# Connectors.net
KiCad netlist of a schematic drawn in Altium Designer
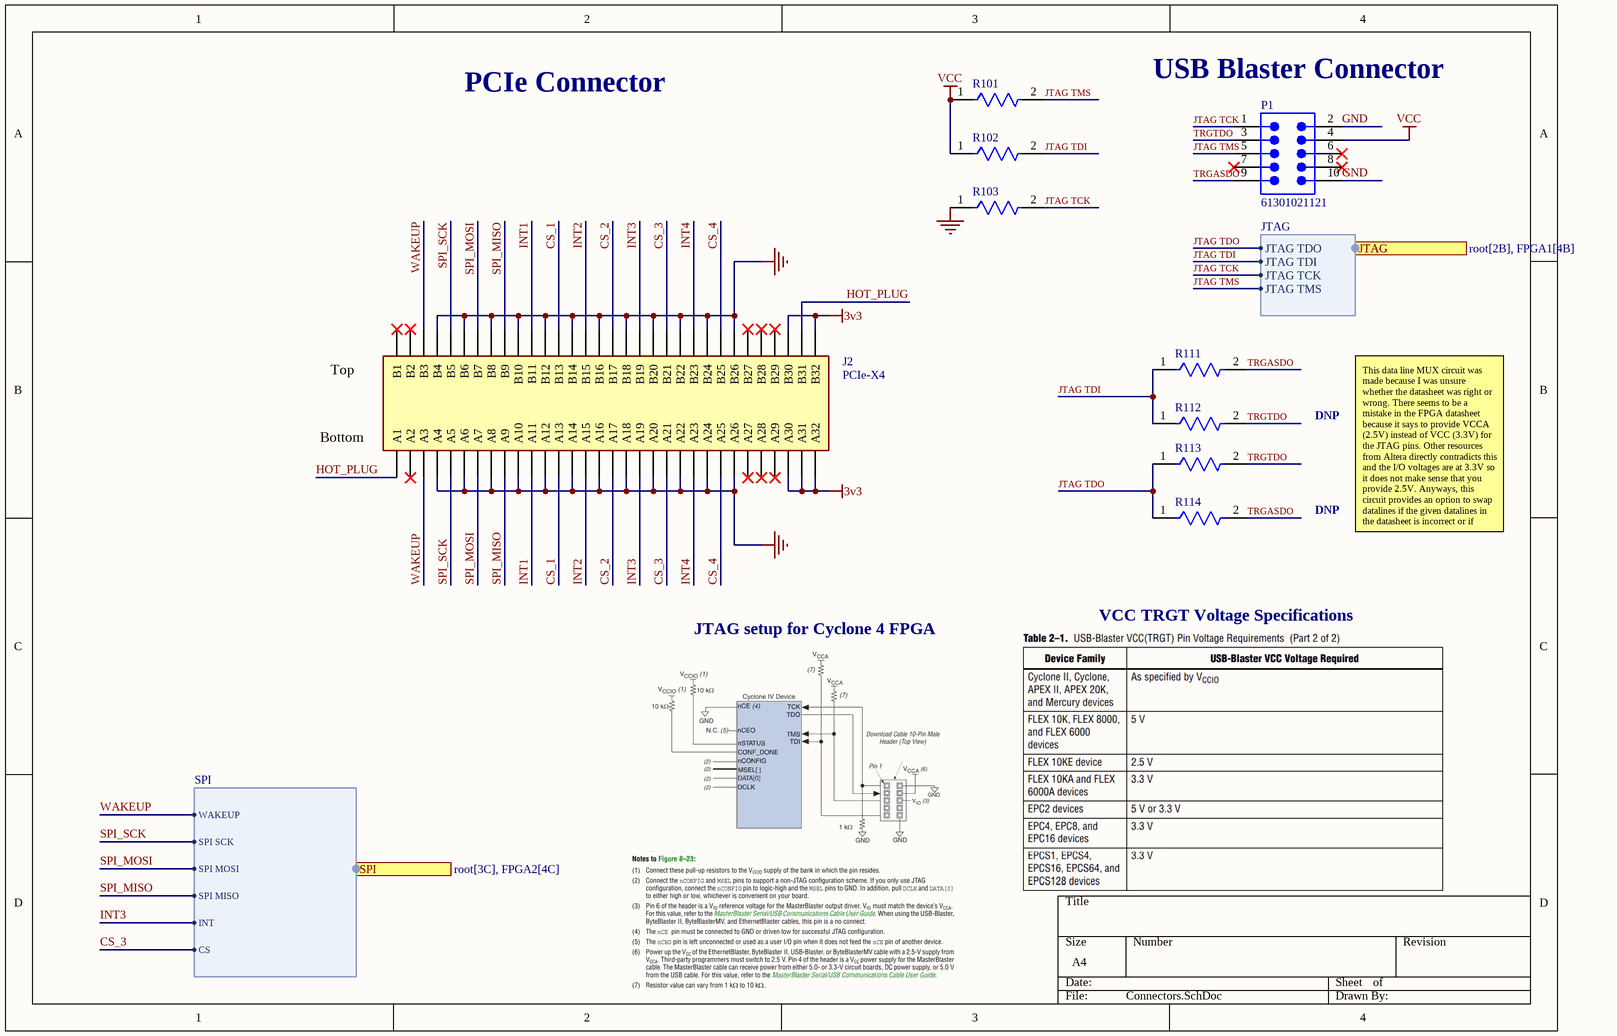
[diagram p0: Connectors.SchDoc]

(export (version "E")
  (design (tool "Eeschema 10.0.6"))
  (components
    (comp (ref "J2")
      (value "PCIe-X4")
      (footprint "BUS_PCIexpress_x4")
      (libsource (lib "FC") (part "PCIe-X4"))
    )
    (comp (ref "P1")
      (value "61301021121")
      (footprint "61301021121")
      (description "THT Vertical Pin Header WR-PHD, Pitch 2.54 mm, Dual Row, 10 pins")
      (libsource (lib "Altium Content Vault") (part "Header_Male_2R_10P"))
    )
    (comp (ref "R101")
      (value "RC0402FR-071KL")
      (footprint "FP-RC0402-0_4-IPC_A")
      (description "RES 1K OHM 1% 1/16W 0402")
      (fields (field (name "TOLERANCE") "1%"))
      (libsource (lib "Altium Content Vault") (part "1029c3af85768c4190bb7ad29bc67b5"))
    )
    (comp (ref "R102")
      (value "RC0402FR-071KL")
      (footprint "FP-RC0402-0_4-IPC_A")
      (description "RES 1K OHM 1% 1/16W 0402")
      (fields (field (name "TOLERANCE") "1%"))
      (libsource (lib "Altium Content Vault") (part "1029c3af85768c4190bb7ad29bc67b5"))
    )
    (comp (ref "R103")
      (value "RC0402FR-071KL")
      (footprint "FP-RC0402-0_4-IPC_A")
      (description "RES 1K OHM 1% 1/16W 0402")
      (fields (field (name "TOLERANCE") "1%"))
      (libsource (lib "Altium Content Vault") (part "1029c3af85768c4190bb7ad29bc67b5"))
    )
    (comp (ref "R111")
      (value "CRCW12060000ZSTA")
      (footprint "FP-CRCW1206-MFG")
      (description "CRCW12060000ZSTA Zero Ohm Resistor, Jumper, 1206 [3216 Metric], Thick Film, 250 mW, Surface Mount")
      (libsource (lib "Altium Content Vault") (part "1029c3af85768c4190bb7ad29bc67b5"))
    )
    (comp (ref "R112")
      (value "CRCW12060000ZSTA")
      (footprint "FP-CRCW1206-MFG")
      (description "CRCW12060000ZSTA Zero Ohm Resistor, Jumper, 1206 [3216 Metric], Thick Film, 250 mW, Surface Mount")
      (libsource (lib "Altium Content Vault") (part "1029c3af85768c4190bb7ad29bc67b5"))
    )
    (comp (ref "R113")
      (value "CRCW12060000ZSTA")
      (footprint "FP-CRCW1206-MFG")
      (description "CRCW12060000ZSTA Zero Ohm Resistor, Jumper, 1206 [3216 Metric], Thick Film, 250 mW, Surface Mount")
      (libsource (lib "Altium Content Vault") (part "1029c3af85768c4190bb7ad29bc67b5"))
    )
    (comp (ref "R114")
      (value "CRCW12060000ZSTA")
      (footprint "FP-CRCW1206-MFG")
      (description "CRCW12060000ZSTA Zero Ohm Resistor, Jumper, 1206 [3216 Metric], Thick Film, 250 mW, Surface Mount")
      (libsource (lib "Altium Content Vault") (part "1029c3af85768c4190bb7ad29bc67b5"))
    )
  )
  (nets
    (net (code "3") (name "/CS_1") (class "Default")
      (node (ref "J2") (pin "A13") (pinfunction "A13_A13") (pintype "passive"))
      (node (ref "J2") (pin "B13") (pinfunction "B13_B13") (pintype "passive"))
    )
    (net (code "4") (name "/CS_2") (class "Default")
      (node (ref "J2") (pin "A17") (pinfunction "A17_A17") (pintype "passive"))
      (node (ref "J2") (pin "B17") (pinfunction "B17_B17") (pintype "passive"))
    )
    (net (code "5") (name "/CS_3") (class "Default")
      (node (ref "J2") (pin "A21") (pinfunction "A21_A21") (pintype "passive"))
      (node (ref "J2") (pin "B21") (pinfunction "B21_B21") (pintype "passive"))
    )
    (net (code "6") (name "/CS_4") (class "Default")
      (node (ref "J2") (pin "A25") (pinfunction "A25_A25") (pintype "passive"))
      (node (ref "J2") (pin "B25") (pinfunction "B25_B25") (pintype "passive"))
    )
    (net (code "7") (name "/HOT_PLUG") (class "Default")
      (node (ref "J2") (pin "A1") (pinfunction "A1_A1") (pintype "passive"))
      (node (ref "J2") (pin "B31") (pinfunction "B31_B31") (pintype "passive"))
    )
    (net (code "8") (name "/INT1") (class "Default")
      (node (ref "J2") (pin "A11") (pinfunction "A11_A11") (pintype "passive"))
      (node (ref "J2") (pin "B11") (pinfunction "B11_B11") (pintype "passive"))
    )
    (net (code "9") (name "/INT2") (class "Default")
      (node (ref "J2") (pin "A15") (pinfunction "A15_A15") (pintype "passive"))
      (node (ref "J2") (pin "B15") (pinfunction "B15_B15") (pintype "passive"))
    )
    (net (code "10") (name "/INT3") (class "Default")
      (node (ref "J2") (pin "A19") (pinfunction "A19_A19") (pintype "passive"))
      (node (ref "J2") (pin "B19") (pinfunction "B19_B19") (pintype "passive"))
    )
    (net (code "11") (name "/INT4") (class "Default")
      (node (ref "J2") (pin "A23") (pinfunction "A23_A23") (pintype "passive"))
      (node (ref "J2") (pin "B23") (pinfunction "B23_B23") (pintype "passive"))
    )
    (net (code "12") (name "/JTAG TCK") (class "Default")
      (node (ref "P1") (pin "1") (pinfunction "1_1") (pintype "passive"))
      (node (ref "R103") (pin "2") (pinfunction "2_2") (pintype "passive"))
    )
    (net (code "13") (name "/JTAG TDI") (class "Default")
      (node (ref "R102") (pin "2") (pinfunction "2_2") (pintype "passive"))
      (node (ref "R111") (pin "1") (pinfunction "1_1") (pintype "passive"))
      (node (ref "R112") (pin "1") (pinfunction "1_1") (pintype "passive"))
    )
    (net (code "14") (name "/JTAG TDO") (class "Default")
      (node (ref "R113") (pin "1") (pinfunction "1_1") (pintype "passive"))
      (node (ref "R114") (pin "1") (pinfunction "1_1") (pintype "passive"))
    )
    (net (code "15") (name "/JTAG TMS") (class "Default")
      (node (ref "P1") (pin "5") (pinfunction "5_5") (pintype "passive"))
      (node (ref "R101") (pin "2") (pinfunction "2_2") (pintype "passive"))
    )
    (net (code "16") (name "/SPI_MISO") (class "Default")
      (node (ref "J2") (pin "A9") (pinfunction "A9_A9") (pintype "passive"))
      (node (ref "J2") (pin "B9") (pinfunction "B9_B9") (pintype "passive"))
    )
    (net (code "17") (name "/SPI_MOSI") (class "Default")
      (node (ref "J2") (pin "A7") (pinfunction "A7_A7") (pintype "passive"))
      (node (ref "J2") (pin "B7") (pinfunction "B7_B7") (pintype "passive"))
    )
    (net (code "18") (name "/SPI_SCK") (class "Default")
      (node (ref "J2") (pin "A5") (pinfunction "A5_A5") (pintype "passive"))
      (node (ref "J2") (pin "B5") (pinfunction "B5_B5") (pintype "passive"))
    )
    (net (code "19") (name "/TRGASDO") (class "Default")
      (node (ref "P1") (pin "9") (pinfunction "9_9") (pintype "passive"))
      (node (ref "R111") (pin "2") (pinfunction "2_2") (pintype "passive"))
      (node (ref "R114") (pin "2") (pinfunction "2_2") (pintype "passive"))
    )
    (net (code "20") (name "/TRGTDO") (class "Default")
      (node (ref "P1") (pin "3") (pinfunction "3_3") (pintype "passive"))
      (node (ref "R112") (pin "2") (pinfunction "2_2") (pintype "passive"))
      (node (ref "R113") (pin "2") (pinfunction "2_2") (pintype "passive"))
    )
    (net (code "21") (name "/WAKEUP") (class "Default")
      (node (ref "J2") (pin "A3") (pinfunction "A3_A3") (pintype "passive"))
      (node (ref "J2") (pin "B3") (pinfunction "B3_B3") (pintype "passive"))
    )
    (net (code "24") (name "3v3") (class "Default")
      (node (ref "J2") (pin "A30") (pinfunction "A30_A30") (pintype "passive"))
      (node (ref "J2") (pin "A31") (pinfunction "A31_A31") (pintype "passive"))
      (node (ref "J2") (pin "A32") (pinfunction "A32_A32") (pintype "passive"))
      (node (ref "J2") (pin "B30") (pinfunction "B30_B30") (pintype "passive"))
      (node (ref "J2") (pin "B32") (pinfunction "B32_B32") (pintype "passive"))
    )
    (net (code "25") (name "GND") (class "Default")
      (node (ref "J2") (pin "A10") (pinfunction "A10_A10") (pintype "passive"))
      (node (ref "J2") (pin "A12") (pinfunction "A12_A12") (pintype "passive"))
      (node (ref "J2") (pin "A14") (pinfunction "A14_A14") (pintype "passive"))
      (node (ref "J2") (pin "A16") (pinfunction "A16_A16") (pintype "passive"))
      (node (ref "J2") (pin "A18") (pinfunction "A18_A18") (pintype "passive"))
      (node (ref "J2") (pin "A20") (pinfunction "A20_A20") (pintype "passive"))
      (node (ref "J2") (pin "A22") (pinfunction "A22_A22") (pintype "passive"))
      (node (ref "J2") (pin "A24") (pinfunction "A24_A24") (pintype "passive"))
      (node (ref "J2") (pin "A26") (pinfunction "A26_A26") (pintype "passive"))
      (node (ref "J2") (pin "A4") (pinfunction "A4_A4") (pintype "passive"))
      (node (ref "J2") (pin "A6") (pinfunction "A6_A6") (pintype "passive"))
      (node (ref "J2") (pin "A8") (pinfunction "A8_A8") (pintype "passive"))
      (node (ref "J2") (pin "B10") (pinfunction "B10_B10") (pintype "passive"))
      (node (ref "J2") (pin "B12") (pinfunction "B12_B12") (pintype "passive"))
      (node (ref "J2") (pin "B14") (pinfunction "B14_B14") (pintype "passive"))
      (node (ref "J2") (pin "B16") (pinfunction "B16_B16") (pintype "passive"))
      (node (ref "J2") (pin "B18") (pinfunction "B18_B18") (pintype "passive"))
      (node (ref "J2") (pin "B20") (pinfunction "B20_B20") (pintype "passive"))
      (node (ref "J2") (pin "B22") (pinfunction "B22_B22") (pintype "passive"))
      (node (ref "J2") (pin "B24") (pinfunction "B24_B24") (pintype "passive"))
      (node (ref "J2") (pin "B26") (pinfunction "B26_B26") (pintype "passive"))
      (node (ref "J2") (pin "B4") (pinfunction "B4_B4") (pintype "passive"))
      (node (ref "J2") (pin "B6") (pinfunction "B6_B6") (pintype "passive"))
      (node (ref "J2") (pin "B8") (pinfunction "B8_B8") (pintype "passive"))
      (node (ref "P1") (pin "10") (pinfunction "10_10") (pintype "passive"))
      (node (ref "P1") (pin "2") (pinfunction "2_2") (pintype "passive"))
      (node (ref "R103") (pin "1") (pinfunction "1_1") (pintype "passive"))
    )
    (net (code "26") (name "VCC") (class "Default")
      (node (ref "P1") (pin "4") (pinfunction "4_4") (pintype "passive"))
      (node (ref "R101") (pin "1") (pinfunction "1_1") (pintype "passive"))
      (node (ref "R102") (pin "1") (pinfunction "1_1") (pintype "passive"))
    )
    (net (code "27") (name "unconnected-(J2-PadA2)") (class "Default")
      (node (ref "J2") (pin "A2") (pinfunction "A2_A2") (pintype "passive+no_connect"))
    )
    (net (code "28") (name "unconnected-(J2-PadA27)") (class "Default")
      (node (ref "J2") (pin "A27") (pinfunction "A27_A27") (pintype "passive+no_connect"))
    )
    (net (code "29") (name "unconnected-(J2-PadA28)") (class "Default")
      (node (ref "J2") (pin "A28") (pinfunction "A28_A28") (pintype "passive+no_connect"))
    )
    (net (code "30") (name "unconnected-(J2-PadA29)") (class "Default")
      (node (ref "J2") (pin "A29") (pinfunction "A29_A29") (pintype "passive+no_connect"))
    )
    (net (code "31") (name "unconnected-(J2-PadB1)") (class "Default")
      (node (ref "J2") (pin "B1") (pinfunction "B1_B1") (pintype "passive+no_connect"))
    )
    (net (code "32") (name "unconnected-(J2-PadB2)") (class "Default")
      (node (ref "J2") (pin "B2") (pinfunction "B2_B2") (pintype "passive+no_connect"))
    )
    (net (code "33") (name "unconnected-(J2-PadB27)") (class "Default")
      (node (ref "J2") (pin "B27") (pinfunction "B27_B27") (pintype "passive+no_connect"))
    )
    (net (code "34") (name "unconnected-(J2-PadB28)") (class "Default")
      (node (ref "J2") (pin "B28") (pinfunction "B28_B28") (pintype "passive+no_connect"))
    )
    (net (code "35") (name "unconnected-(J2-PadB29)") (class "Default")
      (node (ref "J2") (pin "B29") (pinfunction "B29_B29") (pintype "passive+no_connect"))
    )
    (net (code "36") (name "unconnected-(P1-Pad6)") (class "Default")
      (node (ref "P1") (pin "6") (pinfunction "6_6") (pintype "passive+no_connect"))
    )
    (net (code "37") (name "unconnected-(P1-Pad7)") (class "Default")
      (node (ref "P1") (pin "7") (pinfunction "7_7") (pintype "passive+no_connect"))
    )
    (net (code "38") (name "unconnected-(P1-Pad8)") (class "Default")
      (node (ref "P1") (pin "8") (pinfunction "8_8") (pintype "passive+no_connect"))
    )
  )
)
